# PIC.net
KiCad netlist of a schematic drawn in Altium Designer
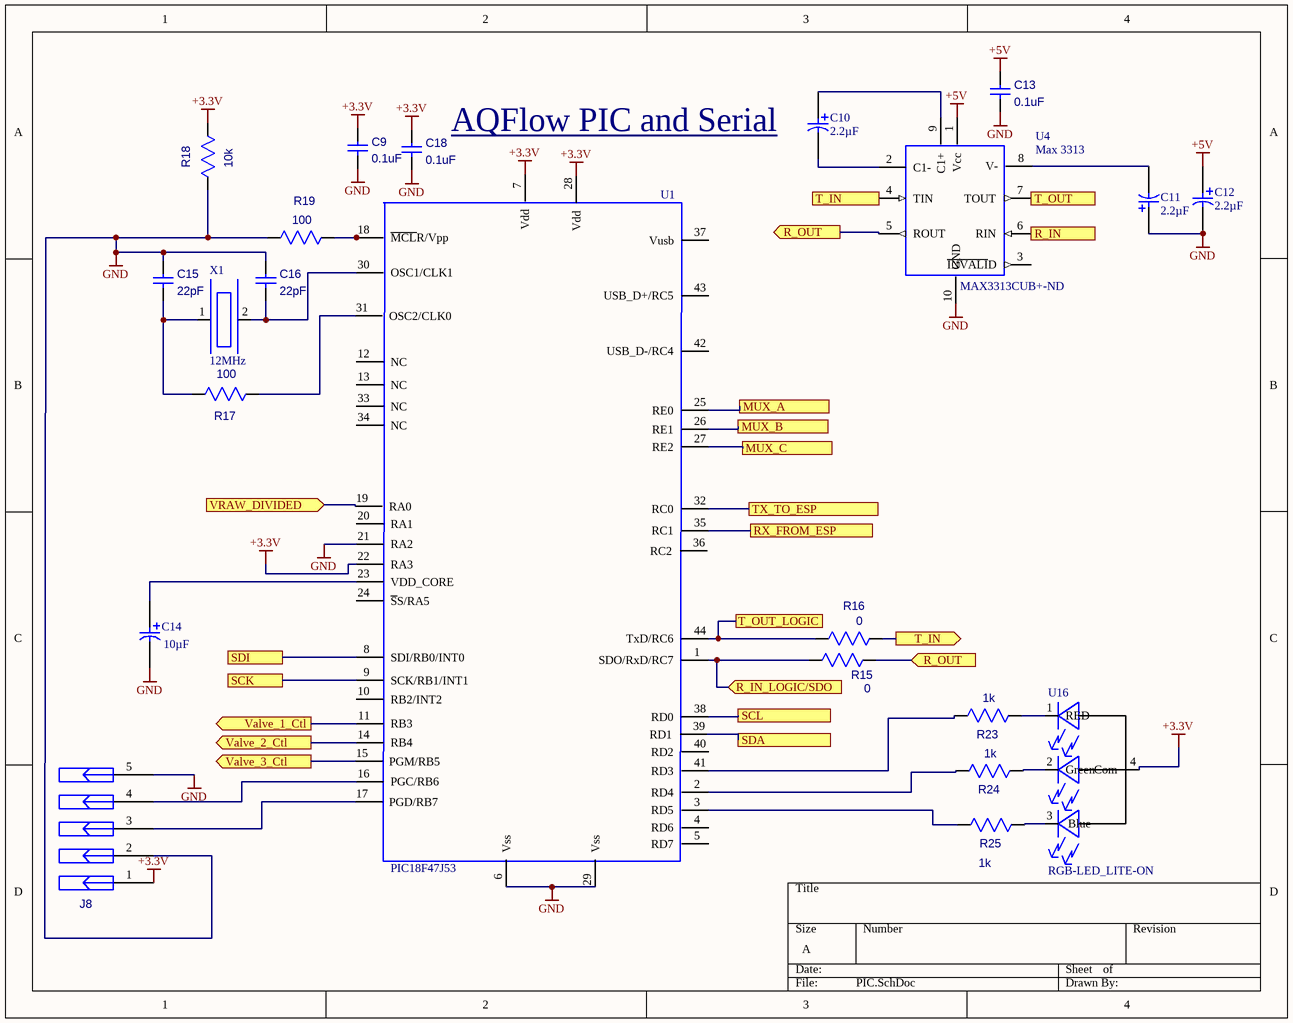
[diagram p0: PIC.SchDoc]

(export (version "E")
  (design (tool "Eeschema 10.0.6"))
  (components
    (comp (ref "C9")
      (value "0.1uF")
      (footprint "CC1206")
      (description "CC1206")
      (libsource (lib "DBNOxVerI") (part "CC1206"))
    )
    (comp (ref "C10")
      (value "Cap_Pol_0805")
      (footprint "Cap_Pol_0805")
      (fields
        (field (name "MANUFACTURER") "AVX Corporation")
        (field (name "MANUFACTURER PART NUMBER") "TAJR225K020RNJ")
        (field (name "CAPACITANCE") "2.2µF")
        (field (name "TOLERANCE") "±10%")
      )
      (libsource (lib "DBNOxVerI") (part "Cap_Pol_0805"))
    )
    (comp (ref "C11")
      (value "Cap_Pol_0805")
      (footprint "Cap_Pol_0805")
      (fields
        (field (name "MANUFACTURER") "AVX Corporation")
        (field (name "MANUFACTURER PART NUMBER") "TAJR225K020RNJ")
        (field (name "CAPACITANCE") "2.2µF")
        (field (name "TOLERANCE") "±10%")
      )
      (libsource (lib "DBNOxVerI") (part "Cap_Pol_0805"))
    )
    (comp (ref "C12")
      (value "Cap_Pol_0805")
      (footprint "Cap_Pol_0805")
      (fields
        (field (name "MANUFACTURER") "AVX Corporation")
        (field (name "MANUFACTURER PART NUMBER") "TAJR225K020RNJ")
        (field (name "CAPACITANCE") "2.2µF")
        (field (name "TOLERANCE") "±10%")
      )
      (libsource (lib "DBNOxVerI") (part "Cap_Pol_0805"))
    )
    (comp (ref "C13")
      (value "0.1uF")
      (footprint "CC1206")
      (description "CC1206")
      (libsource (lib "DBNOxVerI") (part "CC1206"))
    )
    (comp (ref "C14")
      (value "CAP_POL_0805 Generic")
      (footprint "Cap_Pol_0805")
      (fields
        (field (name "MANUFACTURER") "Rohm Semiconductor")
        (field (name "MANUFACTURER PART NUMBER") "TCTP1C106M8R")
        (field (name "CAPACITANCE") "10µF")
        (field (name "TOLERANCE") "±20%")
      )
      (libsource (lib "DBNOxVerI") (part "CAP_POL_0805 Generic"))
    )
    (comp (ref "C15")
      (value "22pF")
      (footprint "CC1206")
      (description "CC1206")
      (libsource (lib "DBNOxVerI") (part "CC1206"))
    )
    (comp (ref "C16")
      (value "22pF")
      (footprint "CC1206")
      (description "CC1206")
      (libsource (lib "DBNOxVerI") (part "CC1206"))
    )
    (comp (ref "C18")
      (value "0.1uF")
      (footprint "CC1206")
      (description "CC1206")
      (libsource (lib "DBNOxVerI") (part "CC1206"))
    )
    (comp (ref "J8")
      (value "HDR_MTA_5X100")
      (footprint "HDR_MTA_5X100")
      (libsource (lib "DBNOxVerI") (part "HDR_MTA_5X100"))
    )
    (comp (ref "R15")
      (value "0")
      (footprint "RC1206")
      (description "RC1206")
      (libsource (lib "DBNOxVerI") (part "RC1206"))
    )
    (comp (ref "R16")
      (value "0")
      (footprint "RC1206")
      (description "RC1206")
      (libsource (lib "DBNOxVerI") (part "RC1206"))
    )
    (comp (ref "R17")
      (value "100")
      (footprint "RC1206")
      (description "RC1206")
      (libsource (lib "DBNOxVerI") (part "RC1206"))
    )
    (comp (ref "R18")
      (value "10k")
      (footprint "RC1206")
      (description "RC1206")
      (libsource (lib "DBNOxVerI") (part "RC1206"))
    )
    (comp (ref "R19")
      (value "100")
      (footprint "RC1206")
      (description "RC1206")
      (libsource (lib "DBNOxVerI") (part "RC1206"))
    )
    (comp (ref "R23")
      (value "1k")
      (footprint "RC1206")
      (description "RC1206")
      (libsource (lib "DBNOxVerI") (part "RC1206"))
    )
    (comp (ref "R24")
      (value "1k")
      (footprint "RC1206")
      (description "RC1206")
      (libsource (lib "DBNOxVerI") (part "RC1206"))
    )
    (comp (ref "R25")
      (value "1k")
      (footprint "RC1206")
      (description "RC1206")
      (libsource (lib "DBNOxVerI") (part "RC1206"))
    )
    (comp (ref "U1")
      (value "PIC18F47J53")
      (footprint "44-TQFP")
      (description "PIC uController")
      (fields
        (field (name "MANUFACTURER") "Microchip Technology")
        (field (name "MANUFACTURER PART NUMBER") "PIC18F47J53T-I/PT")
      )
      (libsource (lib "DBNOxVerI") (part "PIC18F47J53"))
    )
    (comp (ref "U4")
      (value "Max 3313")
      (footprint "uSOP")
      (fields (field (name "SUPPLIER PART NUMBER 1") "MAX3313CUB+-ND"))
      (libsource (lib "DBNOxVerI") (part "Max 3313"))
    )
    (comp (ref "U16")
      (value "RGB-LED_LITE-ON")
      (footprint "LTST-C19HE1WT")
      (libsource (lib "AQFlow_PCB") (part "RGB-LED_LITE-ON"))
    )
    (comp (ref "X1")
      (value "12MHz")
      (footprint "XTAL_MINI_ABM3")
      (libsource (lib "DBNOxVerI") (part "XTAL_MINI_ABM3"))
    )
  )
  (nets
    (net (code "1") (name "+3.3V") (class "Default")
      (node (ref "C18") (pin "1") (pintype "passive"))
      (node (ref "C9") (pin "1") (pintype "passive"))
      (node (ref "J8") (pin "1") (pinfunction "1_1") (pintype "passive"))
      (node (ref "R18") (pin "1") (pinfunction "1_1") (pintype "passive"))
      (node (ref "U1") (pin "22") (pinfunction "RA3_22") (pintype "passive"))
      (node (ref "U1") (pin "28") (pinfunction "Vdd_28") (pintype "passive"))
      (node (ref "U1") (pin "7") (pinfunction "Vdd_7") (pintype "passive"))
      (node (ref "U16") (pin "4") (pinfunction "Com_4") (pintype "passive"))
    )
    (net (code "2") (name "+5V") (class "Default")
      (node (ref "C12") (pin "plus") (pinfunction "plus_plus") (pintype "passive"))
      (node (ref "C13") (pin "1") (pintype "passive"))
      (node (ref "U4") (pin "1") (pinfunction "Vcc_1") (pintype "power_in"))
    )
    (net (code "3") (name "/MUX_A") (class "Default")
      (node (ref "U1") (pin "25") (pinfunction "RE0_25") (pintype "passive"))
    )
    (net (code "4") (name "/MUX_B") (class "Default")
      (node (ref "U1") (pin "26") (pinfunction "RE1_26") (pintype "passive"))
    )
    (net (code "5") (name "/MUX_C") (class "Default")
      (node (ref "U1") (pin "27") (pinfunction "RE2_27") (pintype "passive"))
    )
    (net (code "6") (name "/RX_FROM_ESP") (class "Default")
      (node (ref "U1") (pin "35") (pinfunction "RC1_35") (pintype "passive"))
    )
    (net (code "7") (name "/R_IN") (class "Default")
      (node (ref "U4") (pin "6") (pinfunction "RIN_6") (pintype "input"))
    )
    (net (code "8") (name "/R_IN_LOGIC{slash}SDO") (class "Default")
      (node (ref "R15") (pin "1") (pinfunction "1_1") (pintype "passive"))
      (node (ref "U1") (pin "1") (pinfunction "SDO/RxD/RC7_1") (pintype "passive"))
    )
    (net (code "9") (name "/R_OUT") (class "Default")
      (node (ref "R15") (pin "2") (pinfunction "2_2") (pintype "passive"))
      (node (ref "U4") (pin "5") (pinfunction "ROUT_5") (pintype "output"))
    )
    (net (code "10") (name "/SCK") (class "Default")
      (node (ref "U1") (pin "9") (pinfunction "SCK/RB1/INT1_9") (pintype "passive"))
    )
    (net (code "11") (name "/SCL") (class "Default")
      (node (ref "U1") (pin "38") (pinfunction "RD0_38") (pintype "passive"))
    )
    (net (code "12") (name "/SDA") (class "Default")
      (node (ref "U1") (pin "39") (pinfunction "RD1_39") (pintype "passive"))
    )
    (net (code "13") (name "/SDI") (class "Default")
      (node (ref "U1") (pin "8") (pinfunction "SDI/RB0/INT0_8") (pintype "passive"))
    )
    (net (code "14") (name "/TX_TO_ESP") (class "Default")
      (node (ref "U1") (pin "32") (pinfunction "RC0_32") (pintype "passive"))
    )
    (net (code "15") (name "/T_IN") (class "Default")
      (node (ref "R16") (pin "2") (pinfunction "2_2") (pintype "passive"))
      (node (ref "U4") (pin "4") (pinfunction "TIN_4") (pintype "input"))
    )
    (net (code "16") (name "/T_OUT") (class "Default")
      (node (ref "U4") (pin "7") (pinfunction "TOUT_7") (pintype "output"))
    )
    (net (code "17") (name "/T_OUT_LOGIC") (class "Default")
      (node (ref "R16") (pin "1") (pinfunction "1_1") (pintype "passive"))
      (node (ref "U1") (pin "44") (pinfunction "TxD/RC6_44") (pintype "passive"))
    )
    (net (code "18") (name "/VRAW_DIVIDED") (class "Default")
      (node (ref "U1") (pin "19") (pinfunction "RA0_19") (pintype "passive"))
    )
    (net (code "19") (name "/Valve_1_Ctl") (class "Default")
      (node (ref "U1") (pin "11") (pinfunction "RB3_11") (pintype "passive"))
    )
    (net (code "20") (name "/Valve_2_Ctl") (class "Default")
      (node (ref "U1") (pin "14") (pinfunction "RB4_14") (pintype "passive"))
    )
    (net (code "21") (name "/Valve_3_Ctl") (class "Default")
      (node (ref "U1") (pin "15") (pinfunction "PGM/RB5_15") (pintype "passive"))
    )
    (net (code "22") (name "GND") (class "Default")
      (node (ref "C11") (pin "plus") (pinfunction "plus_plus") (pintype "passive"))
      (node (ref "C12") (pin "minus") (pinfunction "minus_minus") (pintype "passive"))
      (node (ref "C13") (pin "2") (pintype "passive"))
      (node (ref "C14") (pin "minus") (pinfunction "minus_minus") (pintype "passive"))
      (node (ref "C15") (pin "1") (pintype "passive"))
      (node (ref "C16") (pin "1") (pintype "passive"))
      (node (ref "C18") (pin "2") (pintype "passive"))
      (node (ref "C9") (pin "2") (pintype "passive"))
      (node (ref "J8") (pin "2") (pinfunction "2_2") (pintype "passive"))
      (node (ref "J8") (pin "5") (pinfunction "5_5") (pintype "passive"))
      (node (ref "R18") (pin "2") (pinfunction "2_2") (pintype "passive"))
      (node (ref "R19") (pin "1") (pinfunction "1_1") (pintype "passive"))
      (node (ref "U1") (pin "21") (pinfunction "RA2_21") (pintype "passive"))
      (node (ref "U1") (pin "29") (pinfunction "Vss_29") (pintype "passive"))
      (node (ref "U1") (pin "6") (pinfunction "Vss_6") (pintype "passive"))
      (node (ref "U4") (pin "10") (pinfunction "GND_10") (pintype "power_in"))
    )
    (net (code "23") (name "Net-(C15-Pad2)") (class "Default")
      (node (ref "C15") (pin "2") (pintype "passive"))
      (node (ref "R17") (pin "1") (pinfunction "1_1") (pintype "passive"))
      (node (ref "X1") (pin "1") (pinfunction "1_1") (pintype "passive"))
    )
    (net (code "24") (name "Net-(U1-OSC1{slash}CLK1)") (class "Default")
      (node (ref "C16") (pin "2") (pintype "passive"))
      (node (ref "U1") (pin "30") (pinfunction "OSC1/CLK1_30") (pintype "passive"))
      (node (ref "X1") (pin "2") (pinfunction "2_2") (pintype "passive"))
    )
    (net (code "25") (name "Net-(U1-OSC2{slash}CLK0)") (class "Default")
      (node (ref "R17") (pin "2") (pinfunction "2_2") (pintype "passive"))
      (node (ref "U1") (pin "31") (pinfunction "OSC2/CLK0_31") (pintype "passive"))
    )
    (net (code "26") (name "Net-(U1-PGC{slash}RB6)") (class "Default")
      (node (ref "J8") (pin "4") (pinfunction "4_4") (pintype "passive"))
      (node (ref "U1") (pin "16") (pinfunction "PGC/RB6_16") (pintype "passive"))
    )
    (net (code "27") (name "Net-(U1-PGD{slash}RB7)") (class "Default")
      (node (ref "J8") (pin "3") (pinfunction "3_3") (pintype "passive"))
      (node (ref "U1") (pin "17") (pinfunction "PGD/RB7_17") (pintype "passive"))
    )
    (net (code "28") (name "Net-(U1-RD3)") (class "Default")
      (node (ref "R23") (pin "1") (pinfunction "1_1") (pintype "passive"))
      (node (ref "U1") (pin "41") (pinfunction "RD3_41") (pintype "passive"))
    )
    (net (code "29") (name "Net-(U1-RD4)") (class "Default")
      (node (ref "R24") (pin "1") (pinfunction "1_1") (pintype "passive"))
      (node (ref "U1") (pin "2") (pinfunction "RD4_2") (pintype "passive"))
    )
    (net (code "30") (name "Net-(U1-RD5)") (class "Default")
      (node (ref "R25") (pin "1") (pinfunction "1_1") (pintype "passive"))
      (node (ref "U1") (pin "3") (pinfunction "RD5_3") (pintype "passive"))
    )
    (net (code "31") (name "Net-(U1-VDD_CORE)") (class "Default")
      (node (ref "C14") (pin "plus") (pinfunction "plus_plus") (pintype "passive"))
      (node (ref "U1") (pin "23") (pinfunction "VDD_CORE_23") (pintype "passive"))
    )
    (net (code "32") (name "Net-(U1-~{MCL}R{slash}Vpp)") (class "Default")
      (node (ref "R19") (pin "2") (pinfunction "2_2") (pintype "passive"))
      (node (ref "U1") (pin "18") (pinfunction "~{MCL}R/Vpp_18") (pintype "passive"))
    )
    (net (code "33") (name "Net-(U4-C1+)") (class "Default")
      (node (ref "C10") (pin "plus") (pinfunction "plus_plus") (pintype "passive"))
      (node (ref "U4") (pin "9") (pinfunction "C1+_9") (pintype "power_in"))
    )
    (net (code "34") (name "Net-(U4-C1-)") (class "Default")
      (node (ref "C10") (pin "minus") (pinfunction "minus_minus") (pintype "passive"))
      (node (ref "U4") (pin "2") (pinfunction "C1-_2") (pintype "power_in"))
    )
    (net (code "35") (name "Net-(U4-V-)") (class "Default")
      (node (ref "C11") (pin "minus") (pinfunction "minus_minus") (pintype "passive"))
      (node (ref "U4") (pin "8") (pinfunction "V-_8") (pintype "power_in"))
    )
    (net (code "36") (name "Net-(U16-Blue)") (class "Default")
      (node (ref "R25") (pin "2") (pinfunction "2_2") (pintype "passive"))
      (node (ref "U16") (pin "3") (pinfunction "Blue_3") (pintype "passive"))
    )
    (net (code "37") (name "Net-(U16-Green)") (class "Default")
      (node (ref "R24") (pin "2") (pinfunction "2_2") (pintype "passive"))
      (node (ref "U16") (pin "2") (pinfunction "Green_2") (pintype "passive"))
    )
    (net (code "38") (name "Net-(U16-RED)") (class "Default")
      (node (ref "R23") (pin "2") (pinfunction "2_2") (pintype "passive"))
      (node (ref "U16") (pin "1") (pinfunction "RED_1") (pintype "passive"))
    )
    (net (code "39") (name "unconnected-(U1-NC-Pad12)") (class "Default")
      (node (ref "U1") (pin "12") (pinfunction "NC_12") (pintype "passive"))
    )
    (net (code "40") (name "unconnected-(U1-NC-Pad13)") (class "Default")
      (node (ref "U1") (pin "13") (pinfunction "NC_13") (pintype "passive"))
    )
    (net (code "41") (name "unconnected-(U1-NC-Pad33)") (class "Default")
      (node (ref "U1") (pin "33") (pinfunction "NC_33") (pintype "passive"))
    )
    (net (code "42") (name "unconnected-(U1-NC-Pad34)") (class "Default")
      (node (ref "U1") (pin "34") (pinfunction "NC_34") (pintype "passive"))
    )
    (net (code "43") (name "unconnected-(U1-RA1-Pad20)") (class "Default")
      (node (ref "U1") (pin "20") (pinfunction "RA1_20") (pintype "passive"))
    )
    (net (code "44") (name "unconnected-(U1-RB2{slash}INT2-Pad10)") (class "Default")
      (node (ref "U1") (pin "10") (pinfunction "RB2/INT2_10") (pintype "passive"))
    )
    (net (code "45") (name "unconnected-(U1-RC2-Pad36)") (class "Default")
      (node (ref "U1") (pin "36") (pinfunction "RC2_36") (pintype "passive"))
    )
    (net (code "46") (name "unconnected-(U1-RD2-Pad40)") (class "Default")
      (node (ref "U1") (pin "40") (pinfunction "RD2_40") (pintype "passive"))
    )
    (net (code "47") (name "unconnected-(U1-RD6-Pad4)") (class "Default")
      (node (ref "U1") (pin "4") (pinfunction "RD6_4") (pintype "passive"))
    )
    (net (code "48") (name "unconnected-(U1-RD7-Pad5)") (class "Default")
      (node (ref "U1") (pin "5") (pinfunction "RD7_5") (pintype "passive"))
    )
    (net (code "49") (name "unconnected-(U1-USB_D+{slash}RC5-Pad43)") (class "Default")
      (node (ref "U1") (pin "43") (pinfunction "USB_D+/RC5_43") (pintype "passive"))
    )
    (net (code "50") (name "unconnected-(U1-USB_D-{slash}RC4-Pad42)") (class "Default")
      (node (ref "U1") (pin "42") (pinfunction "USB_D-/RC4_42") (pintype "passive"))
    )
    (net (code "51") (name "unconnected-(U1-Vusb-Pad37)") (class "Default")
      (node (ref "U1") (pin "37") (pinfunction "Vusb_37") (pintype "passive"))
    )
    (net (code "52") (name "unconnected-(U1-~{S}S{slash}RA5-Pad24)") (class "Default")
      (node (ref "U1") (pin "24") (pinfunction "~{S}S/RA5_24") (pintype "passive"))
    )
    (net (code "53") (name "unconnected-(U4-~{INVALI}D-Pad3)") (class "Default")
      (node (ref "U4") (pin "3") (pinfunction "~{INVALI}D_3") (pintype "output"))
    )
  )
)
